# DAC_SET1.net
KiCad netlist of a schematic drawn in Altium Designer
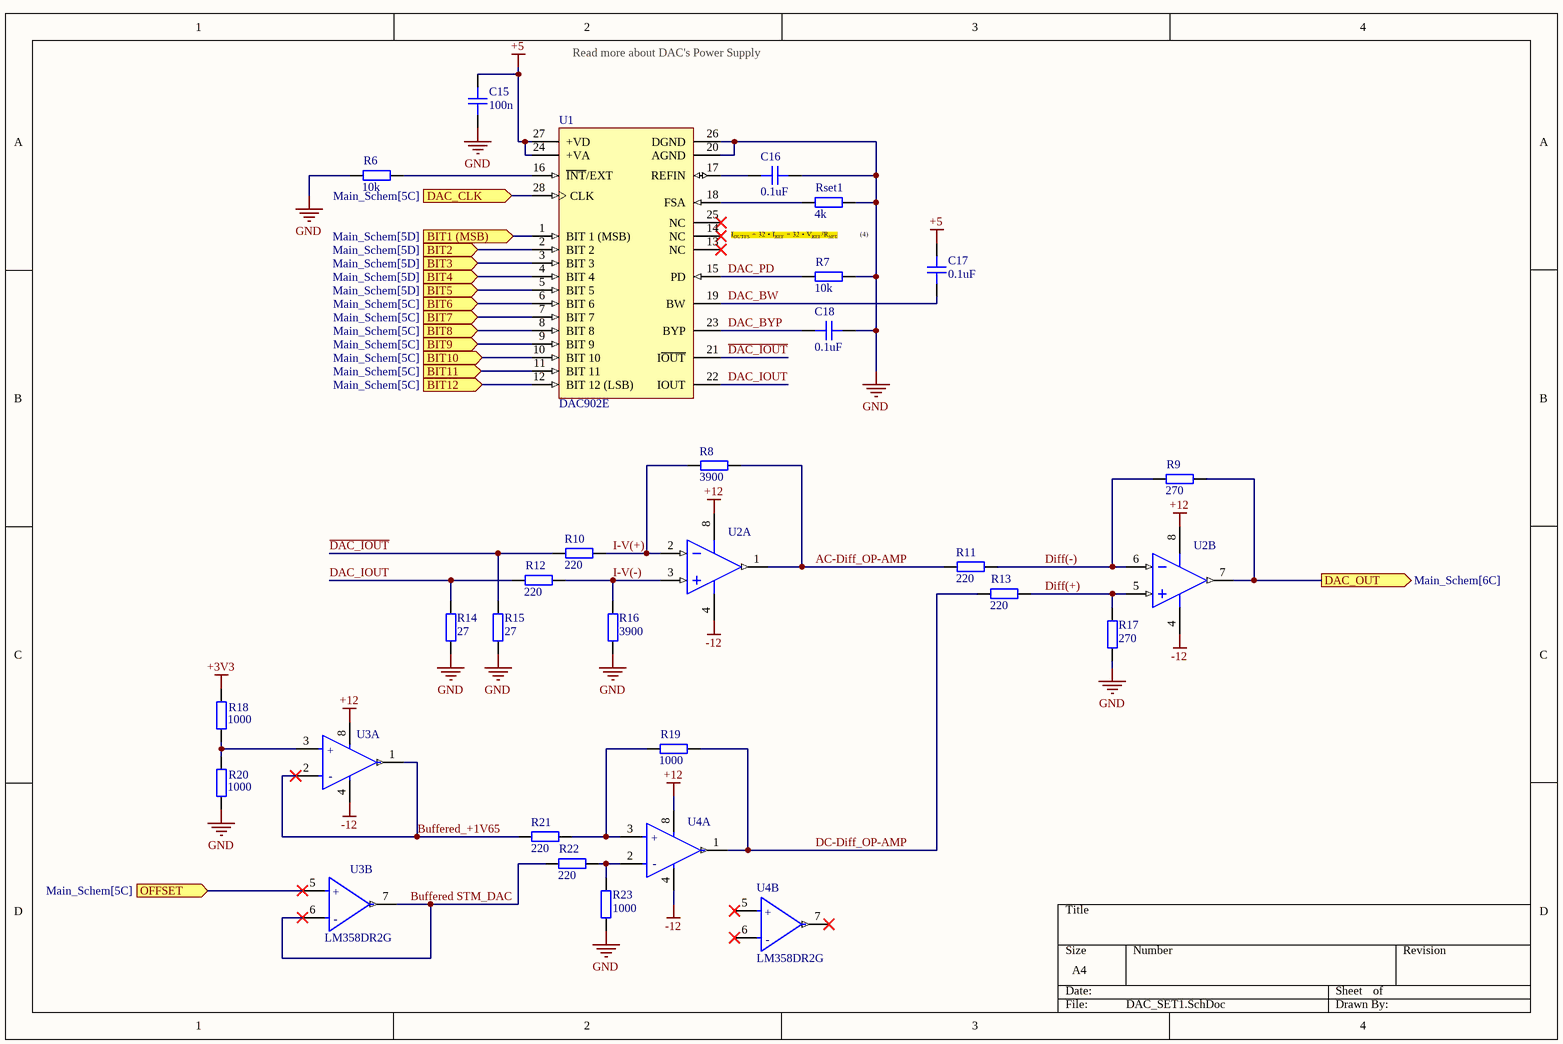
[diagram p0: DAC_SET1.SchDoc]

(export (version "E")
  (design (tool "Eeschema 10.0.6"))
  (components
    (comp (ref "C15")
      (value "100n")
      (footprint "CAP_0805")
      (description "Capacitor SMD 0805")
      (libsource (lib "Schematic-Lib-PhilsLab (1)") (part "CAP_0805"))
    )
    (comp (ref "C16")
      (value "0.1uF")
      (footprint "CAP_1210")
      (description "Capacitor SMD 1210")
      (libsource (lib "Schematic-Lib-PhilsLab (1)") (part "CAP_1210"))
    )
    (comp (ref "C17")
      (value "0.1uF")
      (footprint "CAP_1210")
      (description "Capacitor SMD 1210")
      (libsource (lib "Schematic-Lib-PhilsLab (1)") (part "CAP_1210"))
    )
    (comp (ref "C18")
      (value "0.1uF")
      (footprint "CAP_1210")
      (description "Capacitor SMD 1210")
      (libsource (lib "Schematic-Lib-PhilsLab (1)") (part "CAP_1210"))
    )
    (comp (ref "R6")
      (value "10k")
      (footprint "RES_0805")
      (description "Resistor SMD 0805")
      (libsource (lib "Schematic-Lib-PhilsLab (1)") (part "RES_0805"))
    )
    (comp (ref "R7")
      (value "10k")
      (footprint "RES_0805")
      (description "Resistor SMD 0805")
      (libsource (lib "Schematic-Lib-PhilsLab (1)") (part "RES_0805"))
    )
    (comp (ref "R8")
      (value "3900")
      (footprint "RES_0805")
      (description "Resistor SMD 0805")
      (libsource (lib "Schematic-Lib-PhilsLab (1)") (part "RES_0805"))
    )
    (comp (ref "R9")
      (value "270")
      (footprint "RES_0805")
      (description "Resistor SMD 0805")
      (libsource (lib "Schematic-Lib-PhilsLab (1)") (part "RES_0805"))
    )
    (comp (ref "R10")
      (value "220")
      (footprint "RES_0805")
      (description "Resistor SMD 0805")
      (libsource (lib "Schematic-Lib-PhilsLab (1)") (part "RES_0805"))
    )
    (comp (ref "R11")
      (value "220")
      (footprint "RES_0805")
      (description "Resistor SMD 0805")
      (libsource (lib "Schematic-Lib-PhilsLab (1)") (part "RES_0805"))
    )
    (comp (ref "R12")
      (value "220")
      (footprint "RES_0805")
      (description "Resistor SMD 0805")
      (libsource (lib "Schematic-Lib-PhilsLab (1)") (part "RES_0805"))
    )
    (comp (ref "R13")
      (value "220")
      (footprint "RES_0805")
      (description "Resistor SMD 0805")
      (libsource (lib "Schematic-Lib-PhilsLab (1)") (part "RES_0805"))
    )
    (comp (ref "R14")
      (value "27")
      (footprint "RES_0805")
      (description "Resistor SMD 0805")
      (libsource (lib "Schematic-Lib-PhilsLab (1)") (part "RES_0805"))
    )
    (comp (ref "R15")
      (value "27")
      (footprint "RES_0805")
      (description "Resistor SMD 0805")
      (libsource (lib "Schematic-Lib-PhilsLab (1)") (part "RES_0805"))
    )
    (comp (ref "R16")
      (value "3900")
      (footprint "RES_0805")
      (description "Resistor SMD 0805")
      (libsource (lib "Schematic-Lib-PhilsLab (1)") (part "RES_0805"))
    )
    (comp (ref "R17")
      (value "270")
      (footprint "RES_0805")
      (description "Resistor SMD 0805")
      (libsource (lib "Schematic-Lib-PhilsLab (1)") (part "RES_0805"))
    )
    (comp (ref "R18")
      (value "1000")
      (footprint "RES_0805")
      (description "Resistor SMD 0805")
      (libsource (lib "Schematic-Lib-PhilsLab (1)") (part "RES_0805"))
    )
    (comp (ref "R19")
      (value "1000")
      (footprint "RES_0805")
      (description "Resistor SMD 0805")
      (libsource (lib "Schematic-Lib-PhilsLab (1)") (part "RES_0805"))
    )
    (comp (ref "R20")
      (value "1000")
      (footprint "RES_0805")
      (description "Resistor SMD 0805")
      (libsource (lib "Schematic-Lib-PhilsLab (1)") (part "RES_0805"))
    )
    (comp (ref "R21")
      (value "220")
      (footprint "RES_0805")
      (description "Resistor SMD 0805")
      (libsource (lib "Schematic-Lib-PhilsLab (1)") (part "RES_0805"))
    )
    (comp (ref "R22")
      (value "220")
      (footprint "RES_0805")
      (description "Resistor SMD 0805")
      (libsource (lib "Schematic-Lib-PhilsLab (1)") (part "RES_0805"))
    )
    (comp (ref "R23")
      (value "1000")
      (footprint "RES_0805")
      (description "Resistor SMD 0805")
      (libsource (lib "Schematic-Lib-PhilsLab (1)") (part "RES_0805"))
    )
    (comp (ref "Rset1")
      (value "4k")
      (footprint "RES_0805")
      (description "Resistor SMD 0805")
      (libsource (lib "Schematic-Lib-PhilsLab (1)") (part "RES_0805"))
    )
    (comp (ref "U1")
      (value "DAC902E")
      (footprint "TI-PW28_L")
      (fields (field (name "MANUFACTURER") "Texas Instruments"))
      (libsource (lib "Altium Content Vault") (part "TI-DAC902-28"))
    )
    (comp (ref "U2")
      (value "AD8066ARZ-R7")
      (footprint "ADI-R-8_M")
      (fields (field (name "MANUFACTURER") "Analog Devices") (field (name "GENERIC PART NUMBER") "AD8066"))
      (libsource (lib "Altium Content Vault") (part "ADI-AD80XX-RX-8"))
    )
    (comp (ref "U3")
      (value "LM358DR2G")
      (footprint "FP-751-07-IPC_C")
      (description "IC OPAMP GP 2 CIRCUIT 8SOIC")
      (libsource (lib "Altium Content Vault") (part "992a6607d1d88c80ee6b45e5ba6cb1b"))
    )
    (comp (ref "U4")
      (value "LM358DR2G")
      (footprint "FP-751-07-IPC_C")
      (description "IC OPAMP GP 2 CIRCUIT 8SOIC")
      (libsource (lib "Altium Content Vault") (part "992a6607d1d88c80ee6b45e5ba6cb1b"))
    )
  )
  (nets
    (net (code "1") (name "+3V3") (class "Default")
      (node (ref "R18") (pin "1") (pinfunction "1_1") (pintype "passive"))
    )
    (net (code "2") (name "+5") (class "Default")
      (node (ref "C15") (pin "2") (pinfunction "2_2") (pintype "passive"))
      (node (ref "C17") (pin "2") (pinfunction "2_2") (pintype "passive"))
      (node (ref "U1") (pin "24") (pinfunction "+VA_24") (pintype "power_in"))
      (node (ref "U1") (pin "27") (pinfunction "+VD_27") (pintype "power_in"))
    )
    (net (code "3") (name "+12") (class "Default")
      (node (ref "U2") (pin "8") (pinfunction "+VS_8") (pintype "power_in"))
      (node (ref "U3") (pin "8") (pinfunction "VCC_8") (pintype "power_in"))
      (node (ref "U4") (pin "8") (pinfunction "VCC_8") (pintype "power_in"))
    )
    (net (code "4") (name "-12") (class "Default")
      (node (ref "U2") (pin "4") (pinfunction "-VS_4") (pintype "power_in"))
      (node (ref "U3") (pin "4") (pinfunction "VEE/GND_4") (pintype "power_in"))
      (node (ref "U4") (pin "4") (pinfunction "VEE/GND_4") (pintype "power_in"))
    )
    (net (code "5") (name "/AC-Diff_OP-AMP") (class "Default")
      (node (ref "R11") (pin "2") (pinfunction "2_2") (pintype "passive"))
      (node (ref "R8") (pin "2") (pinfunction "2_2") (pintype "passive"))
      (node (ref "U2") (pin "1") (pinfunction "VOUT_1_1") (pintype "output"))
    )
    (net (code "6") (name "/BIT1 (MSB)") (class "Default")
      (node (ref "U1") (pin "1") (pinfunction "BIT_1_(MSB)_1") (pintype "input"))
    )
    (net (code "7") (name "/BIT2") (class "Default")
      (node (ref "U1") (pin "2") (pinfunction "BIT_2_2") (pintype "input"))
    )
    (net (code "8") (name "/BIT3") (class "Default")
      (node (ref "U1") (pin "3") (pinfunction "BIT_3_3") (pintype "input"))
    )
    (net (code "9") (name "/BIT4") (class "Default")
      (node (ref "U1") (pin "4") (pinfunction "BIT_4_4") (pintype "input"))
    )
    (net (code "10") (name "/BIT5") (class "Default")
      (node (ref "U1") (pin "5") (pinfunction "BIT_5_5") (pintype "input"))
    )
    (net (code "11") (name "/BIT6") (class "Default")
      (node (ref "U1") (pin "6") (pinfunction "BIT_6_6") (pintype "input"))
    )
    (net (code "12") (name "/BIT7") (class "Default")
      (node (ref "U1") (pin "7") (pinfunction "BIT_7_7") (pintype "input"))
    )
    (net (code "13") (name "/BIT8") (class "Default")
      (node (ref "U1") (pin "8") (pinfunction "BIT_8_8") (pintype "input"))
    )
    (net (code "14") (name "/BIT9") (class "Default")
      (node (ref "U1") (pin "9") (pinfunction "BIT_9_9") (pintype "input"))
    )
    (net (code "15") (name "/BIT10") (class "Default")
      (node (ref "U1") (pin "10") (pinfunction "BIT_10_10") (pintype "input"))
    )
    (net (code "16") (name "/BIT11") (class "Default")
      (node (ref "U1") (pin "11") (pinfunction "BIT_11_11") (pintype "input"))
    )
    (net (code "17") (name "/BIT12") (class "Default")
      (node (ref "U1") (pin "12") (pinfunction "BIT_12_(LSB)_12") (pintype "input"))
    )
    (net (code "18") (name "/Buffered STM_DAC") (class "Default")
      (node (ref "R22") (pin "2") (pinfunction "2_2") (pintype "passive"))
      (node (ref "U3") (pin "6") (pinfunction "INPUT_B-_6") (pintype "tri_state"))
      (node (ref "U3") (pin "7") (pinfunction "OUTPUT_B_7") (pintype "output"))
    )
    (net (code "19") (name "/Buffered_+1V65") (class "Default")
      (node (ref "R21") (pin "2") (pinfunction "2_2") (pintype "passive"))
      (node (ref "U3") (pin "1") (pinfunction "OUTPUT_A_1") (pintype "output"))
      (node (ref "U3") (pin "2") (pinfunction "INPUT_A-_2") (pintype "tri_state"))
    )
    (net (code "20") (name "/DAC_BW") (class "Default")
      (node (ref "C17") (pin "1") (pinfunction "1_1") (pintype "passive"))
      (node (ref "U1") (pin "19") (pinfunction "BW_19") (pintype "passive"))
    )
    (net (code "21") (name "/DAC_BYP") (class "Default")
      (node (ref "C18") (pin "1") (pinfunction "1_1") (pintype "passive"))
      (node (ref "U1") (pin "23") (pinfunction "BYP_23") (pintype "passive"))
    )
    (net (code "22") (name "/DAC_CLK") (class "Default")
      (node (ref "U1") (pin "28") (pinfunction "CLK_28") (pintype "input"))
    )
    (net (code "23") (name "/DAC_IOUT") (class "Default")
      (node (ref "R12") (pin "2") (pinfunction "2_2") (pintype "passive"))
      (node (ref "R14") (pin "1") (pinfunction "1_1") (pintype "passive"))
      (node (ref "U1") (pin "22") (pinfunction "IOUT_22") (pintype "tri_state"))
    )
    (net (code "24") (name "/DAC_OUT") (class "Default")
      (node (ref "R9") (pin "1") (pinfunction "1_1") (pintype "passive"))
      (node (ref "U2") (pin "7") (pinfunction "VOUT_2_7") (pintype "output"))
    )
    (net (code "25") (name "/DAC_PD") (class "Default")
      (node (ref "R7") (pin "2") (pinfunction "2_2") (pintype "passive"))
      (node (ref "U1") (pin "15") (pinfunction "PD_15") (pintype "input"))
    )
    (net (code "26") (name "/DC-Diff_OP-AMP") (class "Default")
      (node (ref "R13") (pin "2") (pinfunction "2_2") (pintype "passive"))
      (node (ref "R19") (pin "1") (pinfunction "1_1") (pintype "passive"))
      (node (ref "U4") (pin "1") (pinfunction "OUTPUT_A_1") (pintype "output"))
    )
    (net (code "27") (name "/Diff(+)") (class "Default")
      (node (ref "R13") (pin "1") (pinfunction "1_1") (pintype "passive"))
      (node (ref "R17") (pin "1") (pinfunction "1_1") (pintype "passive"))
      (node (ref "U2") (pin "5") (pinfunction "+IN_2_5") (pintype "input"))
    )
    (net (code "28") (name "/Diff(-)") (class "Default")
      (node (ref "R11") (pin "1") (pinfunction "1_1") (pintype "passive"))
      (node (ref "R9") (pin "2") (pinfunction "2_2") (pintype "passive"))
      (node (ref "U2") (pin "6") (pinfunction "-IN_2_6") (pintype "input"))
    )
    (net (code "29") (name "/I-V(+)") (class "Default")
      (node (ref "R10") (pin "1") (pinfunction "1_1") (pintype "passive"))
      (node (ref "R8") (pin "1") (pinfunction "1_1") (pintype "passive"))
      (node (ref "U2") (pin "2") (pinfunction "-IN_1_2") (pintype "input"))
    )
    (net (code "30") (name "/I-V(-)") (class "Default")
      (node (ref "R12") (pin "1") (pinfunction "1_1") (pintype "passive"))
      (node (ref "R16") (pin "1") (pinfunction "1_1") (pintype "passive"))
      (node (ref "U2") (pin "3") (pinfunction "+IN_1_3") (pintype "input"))
    )
    (net (code "31") (name "/OFFSET") (class "Default")
      (node (ref "U3") (pin "5") (pinfunction "INPUT_B+_5") (pintype "tri_state+no_connect"))
    )
    (net (code "32") (name "/~{DAC_IOUT}") (class "Default")
      (node (ref "R10") (pin "2") (pinfunction "2_2") (pintype "passive"))
      (node (ref "R15") (pin "1") (pinfunction "1_1") (pintype "passive"))
      (node (ref "U1") (pin "21") (pinfunction "I~{OUT}_21") (pintype "tri_state"))
    )
    (net (code "33") (name "GND") (class "Default")
      (node (ref "C15") (pin "1") (pinfunction "1_1") (pintype "passive"))
      (node (ref "C16") (pin "2") (pinfunction "2_2") (pintype "passive"))
      (node (ref "C18") (pin "2") (pinfunction "2_2") (pintype "passive"))
      (node (ref "R14") (pin "2") (pinfunction "2_2") (pintype "passive"))
      (node (ref "R15") (pin "2") (pinfunction "2_2") (pintype "passive"))
      (node (ref "R16") (pin "2") (pinfunction "2_2") (pintype "passive"))
      (node (ref "R17") (pin "2") (pinfunction "2_2") (pintype "passive"))
      (node (ref "R20") (pin "2") (pinfunction "2_2") (pintype "passive"))
      (node (ref "R23") (pin "2") (pinfunction "2_2") (pintype "passive"))
      (node (ref "R6") (pin "2") (pinfunction "2_2") (pintype "passive"))
      (node (ref "R7") (pin "1") (pinfunction "1_1") (pintype "passive"))
      (node (ref "Rset1") (pin "1") (pinfunction "1_1") (pintype "passive"))
      (node (ref "U1") (pin "20") (pinfunction "AGND_20") (pintype "power_in"))
      (node (ref "U1") (pin "26") (pinfunction "DGND_26") (pintype "power_in"))
    )
    (net (code "34") (name "Net-(U1-FSA)") (class "Default")
      (node (ref "Rset1") (pin "2") (pinfunction "2_2") (pintype "passive"))
      (node (ref "U1") (pin "18") (pinfunction "FSA_18") (pintype "input"))
    )
    (net (code "35") (name "Net-(U1-REFIN)") (class "Default")
      (node (ref "C16") (pin "1") (pinfunction "1_1") (pintype "passive"))
      (node (ref "U1") (pin "17") (pinfunction "REFIN_17") (pintype "bidirectional"))
    )
    (net (code "36") (name "Net-(U1-~{INT}{slash}EXT)") (class "Default")
      (node (ref "R6") (pin "1") (pinfunction "1_1") (pintype "passive"))
      (node (ref "U1") (pin "16") (pinfunction "~{INT}/EXT_16") (pintype "input"))
    )
    (net (code "37") (name "Net-(U3A-INPUT_A+)") (class "Default")
      (node (ref "R18") (pin "2") (pinfunction "2_2") (pintype "passive"))
      (node (ref "R20") (pin "1") (pinfunction "1_1") (pintype "passive"))
      (node (ref "U3") (pin "3") (pinfunction "INPUT_A+_3") (pintype "tri_state"))
    )
    (net (code "38") (name "Net-(U4A-INPUT_A+)") (class "Default")
      (node (ref "R19") (pin "2") (pinfunction "2_2") (pintype "passive"))
      (node (ref "R21") (pin "1") (pinfunction "1_1") (pintype "passive"))
      (node (ref "U4") (pin "3") (pinfunction "INPUT_A+_3") (pintype "tri_state"))
    )
    (net (code "39") (name "Net-(U4A-INPUT_A-)") (class "Default")
      (node (ref "R22") (pin "1") (pinfunction "1_1") (pintype "passive"))
      (node (ref "R23") (pin "1") (pinfunction "1_1") (pintype "passive"))
      (node (ref "U4") (pin "2") (pinfunction "INPUT_A-_2") (pintype "tri_state"))
    )
    (net (code "40") (name "unconnected-(U1-NC-Pad13)") (class "Default")
      (node (ref "U1") (pin "13") (pinfunction "NC_13") (pintype "passive+no_connect"))
    )
    (net (code "41") (name "unconnected-(U1-NC-Pad14)") (class "Default")
      (node (ref "U1") (pin "14") (pinfunction "NC_14") (pintype "passive+no_connect"))
    )
    (net (code "42") (name "unconnected-(U1-NC-Pad25)") (class "Default")
      (node (ref "U1") (pin "25") (pinfunction "NC_25") (pintype "passive+no_connect"))
    )
    (net (code "43") (name "unconnected-(U4B-INPUT_B+-Pad5)") (class "Default")
      (node (ref "U4") (pin "5") (pinfunction "INPUT_B+_5") (pintype "tri_state+no_connect"))
    )
    (net (code "44") (name "unconnected-(U4B-INPUT_B--Pad6)") (class "Default")
      (node (ref "U4") (pin "6") (pinfunction "INPUT_B-_6") (pintype "tri_state+no_connect"))
    )
    (net (code "45") (name "unconnected-(U4B-OUTPUT_B-Pad7)") (class "Default")
      (node (ref "U4") (pin "7") (pinfunction "OUTPUT_B_7") (pintype "output+no_connect"))
    )
  )
)
